# ponsettia.net
KiCad netlist of a schematic drawn in EAGLE
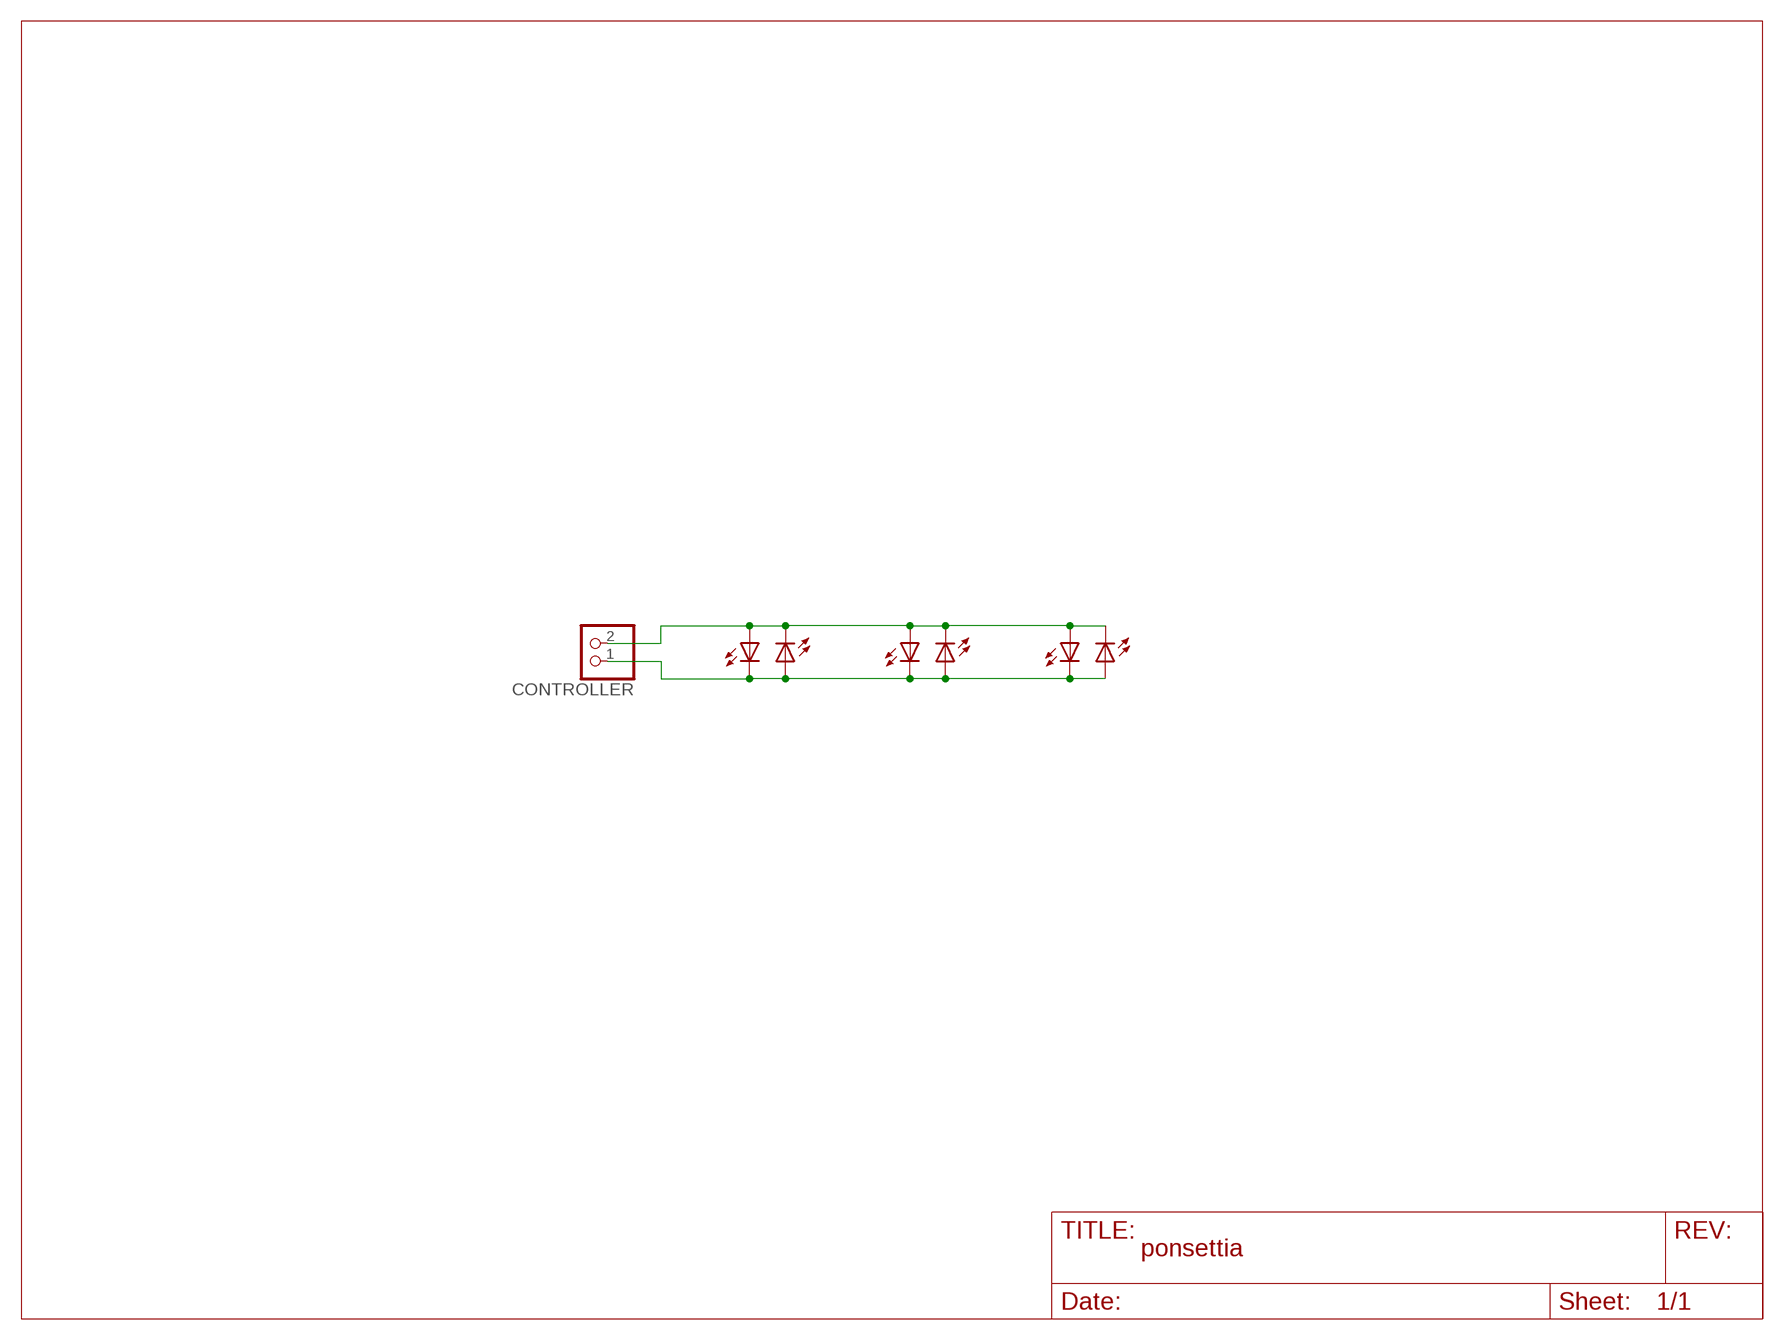
[diagram p0: schematic, sheet 1]

(export (version "E")
  (design (tool "Eeschema 10.0.6"))
  (components
    (comp (ref "CONTROLLER")
      (value "PINHD-1X2")
      (footprint "eagle-import:1X02")
      (libsource (lib "eagle-import") (part "PINHD-1X2"))
    )
    (comp (ref "LED1")
      (value "LED5MM")
      (footprint "eagle-import:LED5MM")
      (libsource (lib "eagle-import") (part "LED5MM"))
    )
    (comp (ref "LED2")
      (value "LED5MM")
      (footprint "eagle-import:LED5MM")
      (libsource (lib "eagle-import") (part "LED5MM"))
    )
    (comp (ref "LED3")
      (value "LED5MM")
      (footprint "eagle-import:LED5MM")
      (libsource (lib "eagle-import") (part "LED5MM"))
    )
    (comp (ref "LED4")
      (value "LED5MM")
      (footprint "eagle-import:LED5MM")
      (libsource (lib "eagle-import") (part "LED5MM"))
    )
    (comp (ref "LED5")
      (value "LED5MM")
      (footprint "eagle-import:LED5MM")
      (libsource (lib "eagle-import") (part "LED5MM"))
    )
    (comp (ref "LED6")
      (value "LED5MM")
      (footprint "eagle-import:LED5MM")
      (libsource (lib "eagle-import") (part "LED5MM"))
    )
  )
  (nets
    (net (code "1") (name "Net-(LED1-C)") (class "Default")
      (node (ref "CONTROLLER") (pin "1") (pinfunction "1_1") (pintype "passive"))
      (node (ref "LED1") (pin "K") (pinfunction "C_K") (pintype "passive"))
      (node (ref "LED2") (pin "A") (pinfunction "A_A") (pintype "passive"))
      (node (ref "LED3") (pin "K") (pinfunction "C_K") (pintype "passive"))
      (node (ref "LED4") (pin "A") (pinfunction "A_A") (pintype "passive"))
      (node (ref "LED5") (pin "K") (pinfunction "C_K") (pintype "passive"))
      (node (ref "LED6") (pin "A") (pinfunction "A_A") (pintype "passive"))
    )
    (net (code "2") (name "Net-(LED2-C)") (class "Default")
      (node (ref "CONTROLLER") (pin "2") (pinfunction "2_2") (pintype "passive"))
      (node (ref "LED1") (pin "A") (pinfunction "A_A") (pintype "passive"))
      (node (ref "LED2") (pin "K") (pinfunction "C_K") (pintype "passive"))
      (node (ref "LED3") (pin "A") (pinfunction "A_A") (pintype "passive"))
      (node (ref "LED4") (pin "K") (pinfunction "C_K") (pintype "passive"))
      (node (ref "LED5") (pin "A") (pinfunction "A_A") (pintype "passive"))
      (node (ref "LED6") (pin "K") (pinfunction "C_K") (pintype "passive"))
    )
  )
)
